# Inline_DC_Panel_Meter.net
KiCad netlist of a schematic drawn in EAGLE
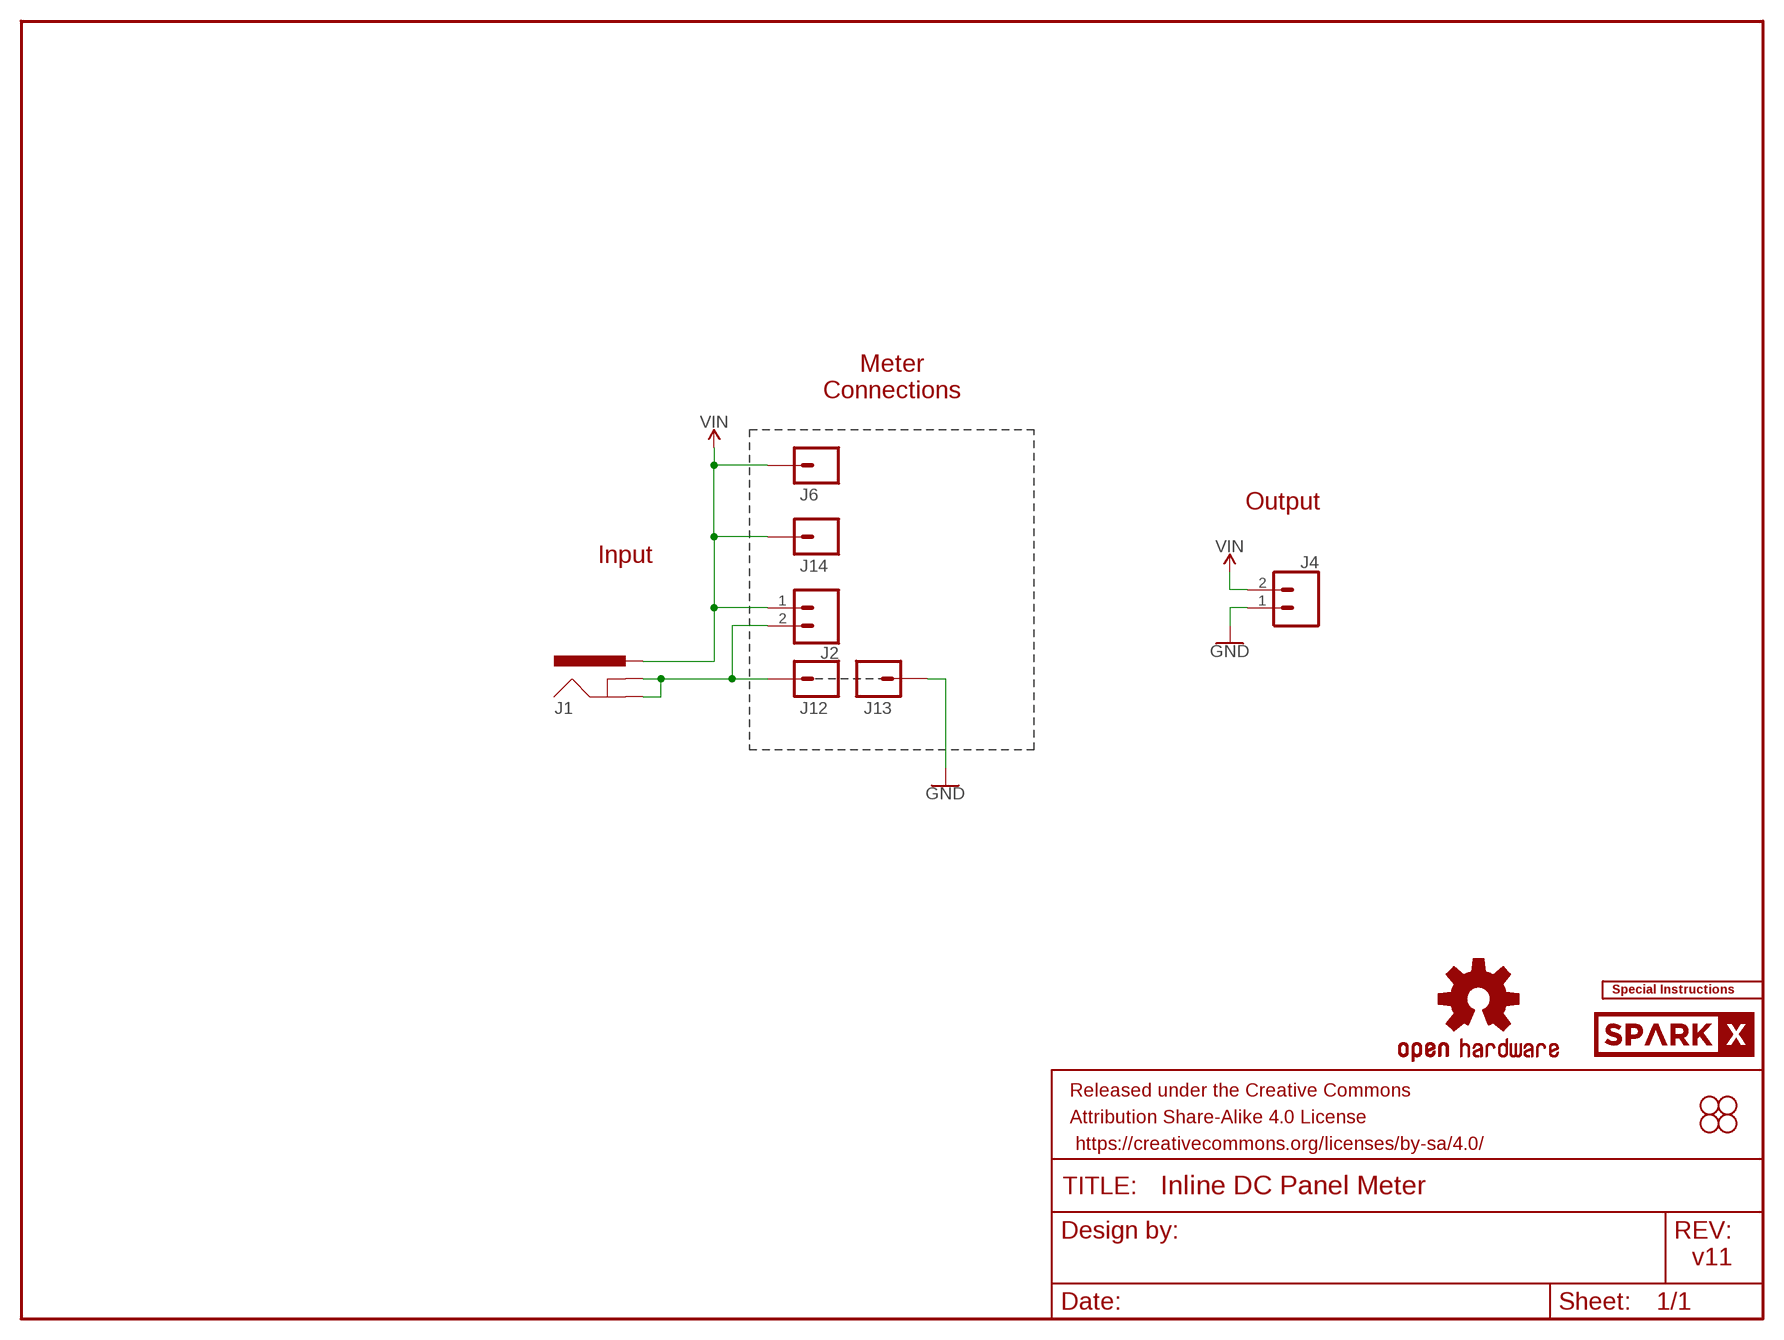
[diagram p0: schematic, sheet 1]

(export (version "E")
  (design (tool "Eeschema 10.0.6"))
  (components
    (comp (ref "FRAME2")
      (value "FRAME-LETTER")
      (footprint "eagle-import:CREATIVE_COMMONS")
      (libsource (lib "eagle-import") (part "FRAME-LETTER"))
    )
    (comp (ref "H1")
      (value "STAND-OFF")
      (footprint "eagle-import:STAND-OFF")
      (libsource (lib "eagle-import") (part "STAND-OFF"))
    )
    (comp (ref "H2")
      (value "STAND-OFF")
      (footprint "eagle-import:STAND-OFF")
      (libsource (lib "eagle-import") (part "STAND-OFF"))
    )
    (comp (ref "H3")
      (value "STAND-OFF")
      (footprint "eagle-import:STAND-OFF")
      (libsource (lib "eagle-import") (part "STAND-OFF"))
    )
    (comp (ref "H4")
      (value "STAND-OFF")
      (footprint "eagle-import:STAND-OFF")
      (libsource (lib "eagle-import") (part "STAND-OFF"))
    )
    (comp (ref "J1")
      (value "POWER_JACKPOWER_JACK_SLOT")
      (footprint "eagle-import:POWER_JACK_PTH_SLOT")
      (libsource (lib "eagle-import") (part "POWER_JACKPOWER_JACK_SLOT"))
    )
    (comp (ref "J2")
      (value "CONN_025MM")
      (footprint "eagle-import:SCREWTERMINAL-5MM-2")
      (libsource (lib "eagle-import") (part "CONN_025MM"))
    )
    (comp (ref "J4")
      (value "CONN_025MM")
      (footprint "eagle-import:SCREWTERMINAL-5MM-2")
      (libsource (lib "eagle-import") (part "CONN_025MM"))
    )
    (comp (ref "J6")
      (value "CONN_01PTH_NO_SILK_YES_STOP")
      (footprint "eagle-import:1X01_NO_SILK")
      (libsource (lib "eagle-import") (part "CONN_01PTH_NO_SILK_YES_STOP"))
    )
    (comp (ref "J12")
      (value "CONN_01PTH_2MM")
      (footprint "eagle-import:1X01_2MM")
      (libsource (lib "eagle-import") (part "CONN_01PTH_2MM"))
    )
    (comp (ref "J13")
      (value "CONN_01PTH_2MM")
      (footprint "eagle-import:1X01_2MM")
      (libsource (lib "eagle-import") (part "CONN_01PTH_2MM"))
    )
    (comp (ref "J14")
      (value "CONN_01PTH_NO_SILK_YES_STOP")
      (footprint "eagle-import:1X01_NO_SILK")
      (libsource (lib "eagle-import") (part "CONN_01PTH_NO_SILK_YES_STOP"))
    )
    (comp (ref "LOGO1")
      (value "OSHW-LOGOS")
      (footprint "eagle-import:OSHW-LOGO-S")
      (libsource (lib "eagle-import") (part "OSHW-LOGOS"))
    )
    (comp (ref "LOGO3")
      (value "SPECIAL_INSTRUCTIONS-ORDERING")
      (footprint "eagle-import:ORDERING_INSTRUCTIONS")
      (libsource (lib "eagle-import") (part "SPECIAL_INSTRUCTIONS-ORDERING"))
    )
    (comp (ref "U$1")
      (value "SPARKX-LOGO5")
      (footprint "eagle-import:SPARKX-LARGE")
      (libsource (lib "eagle-import") (part "SPARKX-LOGO5"))
    )
  )
  (nets
    (net (code "1") (name "GND") (class "Default")
      (node (ref "J13") (pin "1") (pinfunction "1_1") (pintype "passive"))
      (node (ref "J4") (pin "1") (pinfunction "1_1") (pintype "passive"))
    )
    (net (code "2") (name "Net-(J1-PadGND)") (class "Default")
      (node (ref "J1") (pin "GND") (pinfunction "GND_GND") (pintype "bidirectional"))
      (node (ref "J1") (pin "GNDBREAK") (pinfunction "GNDBREAK_GNDBREAK") (pintype "bidirectional"))
      (node (ref "J12") (pin "1") (pinfunction "1_1") (pintype "passive"))
      (node (ref "J2") (pin "2") (pinfunction "2_2") (pintype "passive"))
    )
    (net (code "3") (name "VIN") (class "Default")
      (node (ref "J1") (pin "PWR") (pinfunction "PWR_PWR") (pintype "bidirectional"))
      (node (ref "J14") (pin "1") (pinfunction "1_1") (pintype "passive"))
      (node (ref "J2") (pin "1") (pinfunction "1_1") (pintype "passive"))
      (node (ref "J4") (pin "2") (pinfunction "2_2") (pintype "passive"))
      (node (ref "J6") (pin "1") (pinfunction "1_1") (pintype "passive"))
    )
  )
)
